# EarCon-initial.net
KiCad netlist of a schematic drawn in EAGLE
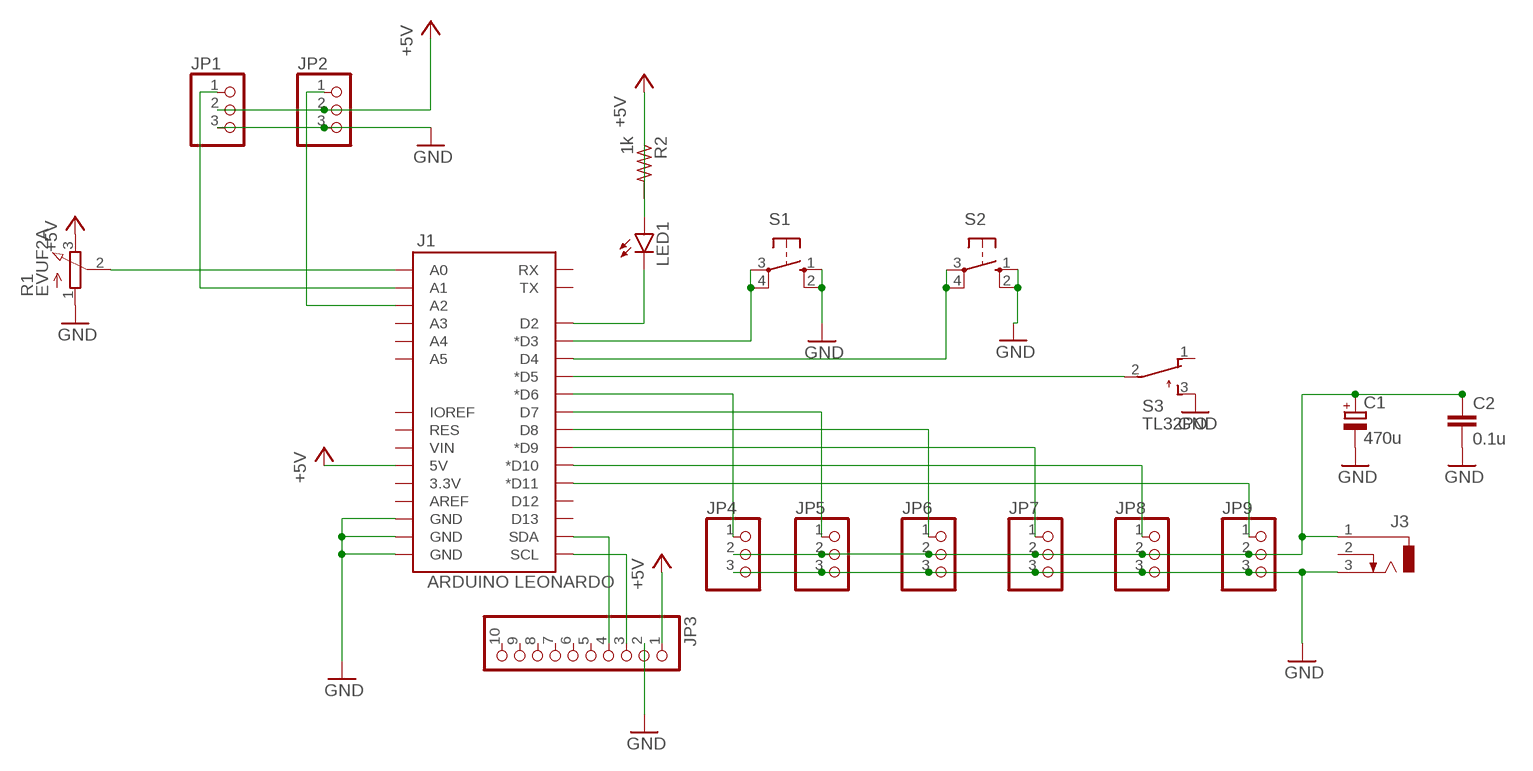
[diagram p0: schematic, sheet 1]

(export (version "E")
  (design (tool "Eeschema 10.0.6"))
  (components
    (comp (ref "C1")
      (value "470u")
      (footprint "eagle-import:E5-10,5")
      (libsource (lib "eagle-import") (part "CPOL-EUE5-10.5"))
    )
    (comp (ref "C2")
      (value "0.1u")
      (footprint "eagle-import:C050-025X075")
      (libsource (lib "eagle-import") (part "C-EU050-025X075"))
    )
    (comp (ref "J1")
      (value "ARDUINO LEONARDO")
      (footprint "eagle-import:UNO_R3_SHIELD_NOLABELS")
      (libsource (lib "eagle-import") (part "ARDUINO_R3_SHIELDNOLABELS"))
    )
    (comp (ref "J3")
      (value "DCJ0303")
      (footprint "eagle-import:DCJ0303")
      (libsource (lib "eagle-import") (part "DCJ0303"))
    )
    (comp (ref "JP1")
      (value "PINHD-1X3")
      (footprint "eagle-import:1X03")
      (libsource (lib "eagle-import") (part "PINHD-1X3"))
    )
    (comp (ref "JP2")
      (value "PINHD-1X3")
      (footprint "eagle-import:1X03")
      (libsource (lib "eagle-import") (part "PINHD-1X3"))
    )
    (comp (ref "JP3")
      (value "PINHD-1X10")
      (footprint "eagle-import:1X10")
      (libsource (lib "eagle-import") (part "PINHD-1X10"))
    )
    (comp (ref "JP4")
      (value "PINHD-1X3")
      (footprint "eagle-import:1X03")
      (libsource (lib "eagle-import") (part "PINHD-1X3"))
    )
    (comp (ref "JP5")
      (value "PINHD-1X3")
      (footprint "eagle-import:1X03")
      (libsource (lib "eagle-import") (part "PINHD-1X3"))
    )
    (comp (ref "JP6")
      (value "PINHD-1X3")
      (footprint "eagle-import:1X03")
      (libsource (lib "eagle-import") (part "PINHD-1X3"))
    )
    (comp (ref "JP7")
      (value "PINHD-1X3")
      (footprint "eagle-import:1X03")
      (libsource (lib "eagle-import") (part "PINHD-1X3"))
    )
    (comp (ref "JP8")
      (value "PINHD-1X3")
      (footprint "eagle-import:1X03")
      (libsource (lib "eagle-import") (part "PINHD-1X3"))
    )
    (comp (ref "JP9")
      (value "PINHD-1X3")
      (footprint "eagle-import:1X03")
      (libsource (lib "eagle-import") (part "PINHD-1X3"))
    )
    (comp (ref "LED1")
      (value "LED5MM")
      (footprint "eagle-import:LED5MM")
      (libsource (lib "eagle-import") (part "LED5MM"))
    )
    (comp (ref "R1")
      (value "EVUF2A")
      (footprint "eagle-import:EVUF")
      (libsource (lib "eagle-import") (part "EVUAF2"))
    )
    (comp (ref "R2")
      (value "1k")
      (footprint "eagle-import:0204_7")
      (libsource (lib "eagle-import") (part "R-US_0204/7"))
    )
    (comp (ref "S1")
      (value "10-XX")
      (footprint "eagle-import:B3F-10XX")
      (fields (field (name "MPN") "B3F-1000"))
      (libsource (lib "eagle-import") (part "10-XX"))
    )
    (comp (ref "S2")
      (value "10-XX")
      (footprint "eagle-import:B3F-10XX")
      (fields (field (name "MPN") "B3F-1000"))
      (libsource (lib "eagle-import") (part "10-XX"))
    )
    (comp (ref "S3")
      (value "TL32PO")
      (footprint "eagle-import:TL3XPO")
      (libsource (lib "eagle-import") (part "TL32PO"))
    )
  )
  (nets
    (net (code "1") (name "+5V") (class "Default")
      (node (ref "J1") (pin "5V") (pinfunction "5V_5V") (pintype "bidirectional"))
      (node (ref "JP1") (pin "2") (pinfunction "2_2") (pintype "passive"))
      (node (ref "JP2") (pin "2") (pinfunction "2_2") (pintype "passive"))
      (node (ref "JP3") (pin "1") (pinfunction "1_1") (pintype "passive"))
      (node (ref "R1") (pin "3") (pinfunction "E_3") (pintype "passive"))
      (node (ref "R2") (pin "2") (pinfunction "2_2") (pintype "passive"))
    )
    (net (code "2") (name "GND") (class "Default")
      (node (ref "C1") (pin "-") (pinfunction "-_-") (pintype "passive"))
      (node (ref "C2") (pin "2") (pinfunction "2_2") (pintype "passive"))
      (node (ref "J1") (pin "GND@0") (pinfunction "GND_GND@0") (pintype "bidirectional"))
      (node (ref "J1") (pin "GND@1") (pinfunction "GND_GND@1") (pintype "bidirectional"))
      (node (ref "J1") (pin "GND@2") (pinfunction "GND_GND@2") (pintype "bidirectional"))
      (node (ref "J3") (pin "3") (pinfunction "3_3") (pintype "passive"))
      (node (ref "JP1") (pin "3") (pinfunction "3_3") (pintype "passive"))
      (node (ref "JP2") (pin "3") (pinfunction "3_3") (pintype "passive"))
      (node (ref "JP3") (pin "2") (pinfunction "2_2") (pintype "passive"))
      (node (ref "JP4") (pin "3") (pinfunction "3_3") (pintype "passive"))
      (node (ref "JP5") (pin "3") (pinfunction "3_3") (pintype "passive"))
      (node (ref "JP6") (pin "3") (pinfunction "3_3") (pintype "passive"))
      (node (ref "JP7") (pin "3") (pinfunction "3_3") (pintype "passive"))
      (node (ref "JP8") (pin "3") (pinfunction "3_3") (pintype "passive"))
      (node (ref "JP9") (pin "3") (pinfunction "3_3") (pintype "passive"))
      (node (ref "R1") (pin "1") (pinfunction "A_1") (pintype "passive"))
      (node (ref "S1") (pin "1") (pinfunction "S_1") (pintype "passive"))
      (node (ref "S1") (pin "2") (pinfunction "S1_2") (pintype "passive"))
      (node (ref "S2") (pin "1") (pinfunction "S_1") (pintype "passive"))
      (node (ref "S2") (pin "2") (pinfunction "S1_2") (pintype "passive"))
      (node (ref "S3") (pin "3") (pinfunction "S_3") (pintype "passive"))
    )
    (net (code "3") (name "Net-(C1-Pad+)") (class "Default")
      (node (ref "C1") (pin "+") (pinfunction "+_+") (pintype "passive"))
      (node (ref "C2") (pin "1") (pinfunction "1_1") (pintype "passive"))
      (node (ref "J3") (pin "1") (pinfunction "1_1") (pintype "passive"))
      (node (ref "JP4") (pin "2") (pinfunction "2_2") (pintype "passive"))
      (node (ref "JP5") (pin "2") (pinfunction "2_2") (pintype "passive"))
      (node (ref "JP6") (pin "2") (pinfunction "2_2") (pintype "passive"))
      (node (ref "JP7") (pin "2") (pinfunction "2_2") (pintype "passive"))
      (node (ref "JP8") (pin "2") (pinfunction "2_2") (pintype "passive"))
      (node (ref "JP9") (pin "2") (pinfunction "2_2") (pintype "passive"))
    )
    (net (code "4") (name "Net-(J1-*D3)") (class "Default")
      (node (ref "J1") (pin "D3") (pinfunction "*D3_D3") (pintype "bidirectional"))
      (node (ref "S1") (pin "3") (pinfunction "P_3") (pintype "passive"))
      (node (ref "S1") (pin "4") (pinfunction "P1_4") (pintype "passive"))
    )
    (net (code "5") (name "Net-(J1-*D5)") (class "Default")
      (node (ref "J1") (pin "D5") (pinfunction "*D5_D5") (pintype "bidirectional"))
      (node (ref "S3") (pin "2") (pinfunction "P_2") (pintype "passive"))
    )
    (net (code "6") (name "Net-(J1-*D6)") (class "Default")
      (node (ref "J1") (pin "D6") (pinfunction "*D6_D6") (pintype "bidirectional"))
      (node (ref "JP4") (pin "1") (pinfunction "1_1") (pintype "passive"))
    )
    (net (code "7") (name "Net-(J1-*D9)") (class "Default")
      (node (ref "J1") (pin "D9") (pinfunction "*D9_D9") (pintype "bidirectional"))
      (node (ref "JP7") (pin "1") (pinfunction "1_1") (pintype "passive"))
    )
    (net (code "8") (name "Net-(J1-*D10)") (class "Default")
      (node (ref "J1") (pin "D10") (pinfunction "*D10_D10") (pintype "bidirectional"))
      (node (ref "JP8") (pin "1") (pinfunction "1_1") (pintype "passive"))
    )
    (net (code "9") (name "Net-(J1-*D11)") (class "Default")
      (node (ref "J1") (pin "D11") (pinfunction "*D11_D11") (pintype "bidirectional"))
      (node (ref "JP9") (pin "1") (pinfunction "1_1") (pintype "passive"))
    )
    (net (code "10") (name "Net-(J1-PadA1)") (class "Default")
      (node (ref "J1") (pin "A1") (pinfunction "A1_A1") (pintype "bidirectional"))
      (node (ref "JP1") (pin "1") (pinfunction "1_1") (pintype "passive"))
    )
    (net (code "11") (name "Net-(J1-PadA2)") (class "Default")
      (node (ref "J1") (pin "A2") (pinfunction "A2_A2") (pintype "bidirectional"))
      (node (ref "JP2") (pin "1") (pinfunction "1_1") (pintype "passive"))
    )
    (net (code "12") (name "Net-(J1-PadD7)") (class "Default")
      (node (ref "J1") (pin "D7") (pinfunction "D7_D7") (pintype "bidirectional"))
      (node (ref "JP5") (pin "1") (pinfunction "1_1") (pintype "passive"))
    )
    (net (code "13") (name "Net-(J1-PadD8)") (class "Default")
      (node (ref "J1") (pin "D8") (pinfunction "D8_D8") (pintype "bidirectional"))
      (node (ref "JP6") (pin "1") (pinfunction "1_1") (pintype "passive"))
    )
    (net (code "14") (name "Net-(J1-PadSCL)") (class "Default")
      (node (ref "J1") (pin "SCL") (pinfunction "SCL_SCL") (pintype "bidirectional"))
      (node (ref "JP3") (pin "3") (pinfunction "3_3") (pintype "passive"))
    )
    (net (code "15") (name "Net-(J1-PadSDA)") (class "Default")
      (node (ref "J1") (pin "SDA") (pinfunction "SDA_SDA") (pintype "bidirectional"))
      (node (ref "JP3") (pin "4") (pinfunction "4_4") (pintype "passive"))
    )
    (net (code "16") (name "Net-(LED1-C)") (class "Default")
      (node (ref "J1") (pin "D2") (pinfunction "D2_D2") (pintype "bidirectional"))
      (node (ref "LED1") (pin "K") (pinfunction "C_K") (pintype "passive"))
    )
    (net (code "17") (name "Net-(LED1-PadA)") (class "Default")
      (node (ref "LED1") (pin "A") (pinfunction "A_A") (pintype "passive"))
      (node (ref "R2") (pin "1") (pinfunction "1_1") (pintype "passive"))
    )
    (net (code "18") (name "Net-(R1-S)") (class "Default")
      (node (ref "J1") (pin "A0") (pinfunction "A0_A0") (pintype "bidirectional"))
      (node (ref "R1") (pin "2") (pinfunction "S_2") (pintype "passive"))
    )
    (net (code "19") (name "Net-(S2-P)") (class "Default")
      (node (ref "J1") (pin "D4") (pinfunction "D4_D4") (pintype "bidirectional"))
      (node (ref "S2") (pin "3") (pinfunction "P_3") (pintype "passive"))
      (node (ref "S2") (pin "4") (pinfunction "P1_4") (pintype "passive"))
    )
    (net (code "20") (name "unconnected-(J1-Pad3.3V)") (class "Default")
      (node (ref "J1") (pin "3.3V") (pinfunction "3.3V_3.3V") (pintype "bidirectional"))
    )
    (net (code "21") (name "unconnected-(J1-PadA3)") (class "Default")
      (node (ref "J1") (pin "A3") (pinfunction "A3_A3") (pintype "bidirectional"))
    )
    (net (code "22") (name "unconnected-(J1-PadA4)") (class "Default")
      (node (ref "J1") (pin "A4") (pinfunction "A4_A4") (pintype "bidirectional"))
    )
    (net (code "23") (name "unconnected-(J1-PadA5)") (class "Default")
      (node (ref "J1") (pin "A5") (pinfunction "A5_A5") (pintype "bidirectional"))
    )
    (net (code "24") (name "unconnected-(J1-PadAREF)") (class "Default")
      (node (ref "J1") (pin "AREF") (pinfunction "AREF_AREF") (pintype "bidirectional"))
    )
    (net (code "25") (name "unconnected-(J1-PadD12)") (class "Default")
      (node (ref "J1") (pin "D12") (pinfunction "D12_D12") (pintype "bidirectional"))
    )
    (net (code "26") (name "unconnected-(J1-PadD13)") (class "Default")
      (node (ref "J1") (pin "D13") (pinfunction "D13_D13") (pintype "bidirectional"))
    )
    (net (code "27") (name "unconnected-(J1-PadIOREF)") (class "Default")
      (node (ref "J1") (pin "IOREF") (pinfunction "IOREF_IOREF") (pintype "bidirectional"))
    )
    (net (code "28") (name "unconnected-(J1-PadRES)") (class "Default")
      (node (ref "J1") (pin "RES") (pinfunction "RES_RES") (pintype "bidirectional"))
    )
    (net (code "29") (name "unconnected-(J1-PadRX)") (class "Default")
      (node (ref "J1") (pin "RX") (pinfunction "RX_RX") (pintype "bidirectional"))
    )
    (net (code "30") (name "unconnected-(J1-PadTX)") (class "Default")
      (node (ref "J1") (pin "TX") (pinfunction "TX_TX") (pintype "bidirectional"))
    )
    (net (code "31") (name "unconnected-(J1-PadVIN)") (class "Default")
      (node (ref "J1") (pin "VIN") (pinfunction "VIN_VIN") (pintype "bidirectional"))
    )
    (net (code "32") (name "unconnected-(J3-Pad2)") (class "Default")
      (node (ref "J3") (pin "2") (pinfunction "2_2") (pintype "passive"))
    )
    (net (code "33") (name "unconnected-(JP3-Pad5)") (class "Default")
      (node (ref "JP3") (pin "5") (pinfunction "5_5") (pintype "passive"))
    )
    (net (code "34") (name "unconnected-(JP3-Pad6)") (class "Default")
      (node (ref "JP3") (pin "6") (pinfunction "6_6") (pintype "passive"))
    )
    (net (code "35") (name "unconnected-(JP3-Pad7)") (class "Default")
      (node (ref "JP3") (pin "7") (pinfunction "7_7") (pintype "passive"))
    )
    (net (code "36") (name "unconnected-(JP3-Pad8)") (class "Default")
      (node (ref "JP3") (pin "8") (pinfunction "8_8") (pintype "passive"))
    )
    (net (code "37") (name "unconnected-(JP3-Pad9)") (class "Default")
      (node (ref "JP3") (pin "9") (pinfunction "9_9") (pintype "passive"))
    )
    (net (code "38") (name "unconnected-(JP3-Pad10)") (class "Default")
      (node (ref "JP3") (pin "10") (pinfunction "10_10") (pintype "passive"))
    )
    (net (code "39") (name "unconnected-(S3-O-Pad1)") (class "Default")
      (node (ref "S3") (pin "1") (pinfunction "O_1") (pintype "passive"))
    )
  )
)
